# nusense-fans.net
KiCad netlist of a schematic drawn in Altium Designer
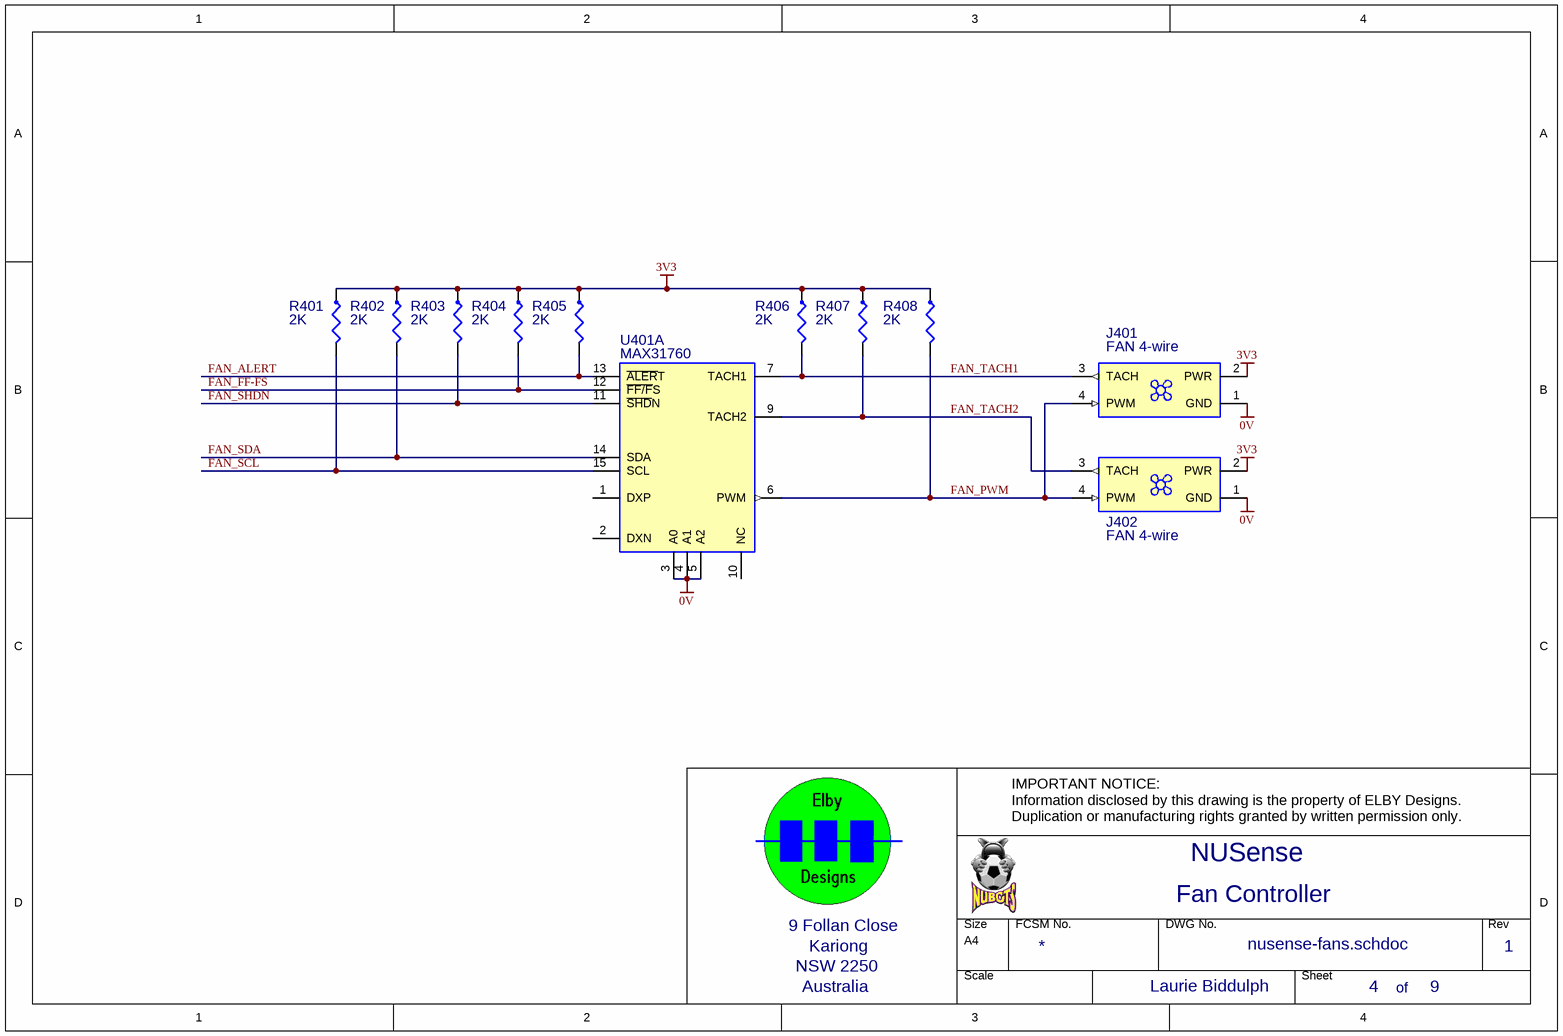
[diagram p0: nusense-fans.schdoc]

(export (version "E")
  (design (tool "Eeschema 10.0.6"))
  (components
    (comp (ref "J401")
      (value "FAN 4-wire")
      (description "4-Wire Fan")
      (libsource (lib "NuBots") (part "FAN-4wire"))
    )
    (comp (ref "J402")
      (value "FAN 4-wire")
      (description "4-Wire Fan")
      (libsource (lib "NuBots") (part "FAN-4wire"))
    )
    (comp (ref "R401")
      (value "2K")
      (footprint "AXIAL-0.4(LB)")
      (description "0.5W 1% Metal Film Resistor")
      (libsource (lib "resistor") (part "RM-2K(LB)"))
    )
    (comp (ref "R402")
      (value "2K")
      (footprint "AXIAL-0.4(LB)")
      (description "0.5W 1% Metal Film Resistor")
      (libsource (lib "resistor") (part "RM-2K(LB)"))
    )
    (comp (ref "R403")
      (value "2K")
      (footprint "AXIAL-0.4(LB)")
      (description "0.5W 1% Metal Film Resistor")
      (libsource (lib "resistor") (part "RM-2K(LB)"))
    )
    (comp (ref "R404")
      (value "2K")
      (footprint "AXIAL-0.4(LB)")
      (description "0.5W 1% Metal Film Resistor")
      (libsource (lib "resistor") (part "RM-2K(LB)"))
    )
    (comp (ref "R405")
      (value "2K")
      (footprint "AXIAL-0.4(LB)")
      (description "0.5W 1% Metal Film Resistor")
      (libsource (lib "resistor") (part "RM-2K(LB)"))
    )
    (comp (ref "R406")
      (value "2K")
      (footprint "AXIAL-0.4(LB)")
      (description "0.5W 1% Metal Film Resistor")
      (libsource (lib "resistor") (part "RM-2K(LB)"))
    )
    (comp (ref "R407")
      (value "2K")
      (footprint "AXIAL-0.4(LB)")
      (description "0.5W 1% Metal Film Resistor")
      (libsource (lib "resistor") (part "RM-2K(LB)"))
    )
    (comp (ref "R408")
      (value "2K")
      (footprint "AXIAL-0.4(LB)")
      (description "0.5W 1% Metal Film Resistor")
      (libsource (lib "resistor") (part "RM-2K(LB)"))
    )
    (comp (ref "U401")
      (value "MAX31760")
      (description "Precision Fan Speed")
      (libsource (lib "NuBots") (part "MAX31760"))
    )
  )
  (nets
    (net (code "1") (name "/FAN_ALERT") (class "Default")
      (node (ref "R405") (pin "2") (pinfunction "2_2") (pintype "passive"))
      (node (ref "U401") (pin "13") (pinfunction "~{ALER}T_13") (pintype "passive"))
    )
    (net (code "2") (name "/FAN_FF-FS") (class "Default")
      (node (ref "R404") (pin "2") (pinfunction "2_2") (pintype "passive"))
      (node (ref "U401") (pin "12") (pinfunction "~{FF/F}S_12") (pintype "passive"))
    )
    (net (code "3") (name "/FAN_PWM") (class "Default")
      (node (ref "J401") (pin "4") (pinfunction "PWM_4") (pintype "input"))
      (node (ref "J402") (pin "4") (pinfunction "PWM_4") (pintype "input"))
      (node (ref "R408") (pin "2") (pinfunction "2_2") (pintype "passive"))
      (node (ref "U401") (pin "6") (pinfunction "PWM_6") (pintype "output"))
    )
    (net (code "4") (name "/FAN_SCL") (class "Default")
      (node (ref "R401") (pin "2") (pinfunction "2_2") (pintype "passive"))
      (node (ref "U401") (pin "15") (pinfunction "SCL_15") (pintype "passive"))
    )
    (net (code "5") (name "/FAN_SDA") (class "Default")
      (node (ref "R402") (pin "2") (pinfunction "2_2") (pintype "passive"))
      (node (ref "U401") (pin "14") (pinfunction "SDA_14") (pintype "passive"))
    )
    (net (code "6") (name "/FAN_SHDN") (class "Default")
      (node (ref "R403") (pin "2") (pinfunction "2_2") (pintype "passive"))
      (node (ref "U401") (pin "11") (pinfunction "~{SHD}N_11") (pintype "passive"))
    )
    (net (code "7") (name "/FAN_TACH1") (class "Default")
      (node (ref "J401") (pin "3") (pinfunction "TACH_3") (pintype "output"))
      (node (ref "R406") (pin "2") (pinfunction "2_2") (pintype "passive"))
      (node (ref "U401") (pin "7") (pinfunction "TACH1_7") (pintype "passive"))
    )
    (net (code "8") (name "/FAN_TACH2") (class "Default")
      (node (ref "J402") (pin "3") (pinfunction "TACH_3") (pintype "output"))
      (node (ref "R407") (pin "2") (pinfunction "2_2") (pintype "passive"))
      (node (ref "U401") (pin "9") (pinfunction "TACH2_9") (pintype "passive"))
    )
    (net (code "9") (name "0V") (class "Default")
      (node (ref "J401") (pin "1") (pinfunction "GND_1") (pintype "power_in"))
      (node (ref "J402") (pin "1") (pinfunction "GND_1") (pintype "power_in"))
      (node (ref "U401") (pin "3") (pinfunction "A0_3") (pintype "passive"))
      (node (ref "U401") (pin "4") (pinfunction "A1_4") (pintype "passive"))
      (node (ref "U401") (pin "5") (pinfunction "A2_5") (pintype "passive"))
    )
    (net (code "10") (name "3V3") (class "Default")
      (node (ref "J401") (pin "2") (pinfunction "PWR_2") (pintype "power_in"))
      (node (ref "J402") (pin "2") (pinfunction "PWR_2") (pintype "power_in"))
      (node (ref "R401") (pin "1") (pinfunction "1_1") (pintype "passive"))
      (node (ref "R402") (pin "1") (pinfunction "1_1") (pintype "passive"))
      (node (ref "R403") (pin "1") (pinfunction "1_1") (pintype "passive"))
      (node (ref "R404") (pin "1") (pinfunction "1_1") (pintype "passive"))
      (node (ref "R405") (pin "1") (pinfunction "1_1") (pintype "passive"))
      (node (ref "R406") (pin "1") (pinfunction "1_1") (pintype "passive"))
      (node (ref "R407") (pin "1") (pinfunction "1_1") (pintype "passive"))
      (node (ref "R408") (pin "1") (pinfunction "1_1") (pintype "passive"))
    )
    (net (code "11") (name "unconnected-(U401A-DXN-Pad2)") (class "Default")
      (node (ref "U401") (pin "2") (pinfunction "DXN_2") (pintype "passive"))
    )
    (net (code "12") (name "unconnected-(U401A-DXP-Pad1)") (class "Default")
      (node (ref "U401") (pin "1") (pinfunction "DXP_1") (pintype "passive"))
    )
    (net (code "13") (name "unconnected-(U401A-NC-Pad10)") (class "Default")
      (node (ref "U401") (pin "10") (pinfunction "NC_10") (pintype "passive"))
    )
  )
)
